# CON_MEZZANINE_GPIO_JTAG.net
KiCad netlist of a schematic drawn in Altium Designer
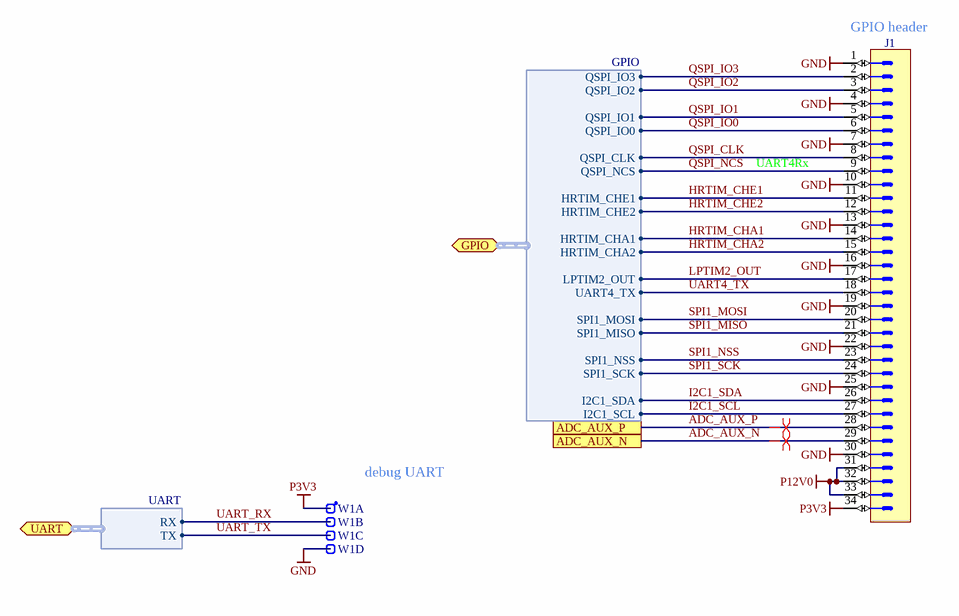
[diagram p0: CON_MEZZANINE_GPIO_JTAG.SchDoc]

(export (version "E")
  (design (tool "Eeschema 10.0.6"))
  (components
    (comp (ref "J1")
      (value "Header 34")
      (footprint "3M_N2534-6002RB")
      (description "Connector 34 Male")
      (fields
        (field (name "PART NUMBER") "3M_N2534-6002RB")
        (field (name "MANUFACTURER") "3M")
        (field (name "AUTHOR") "CERN DEM JLC")
      )
      (libsource (lib "Connectors") (part "Connector 34 Male"))
    )
    (comp (ref "W1")
      (value "Header 4")
      (footprint "SAMTEC_HTSW-104-23-L-S")
      (description "4 Mini Wire-Wrap Contact Strip Header")
      (fields
        (field (name "PART NUMBER") "SAMTEC_HTSW-104-23-L-S")
        (field (name "MANUFACTURER") "SAMTEC")
        (field (name "AUTHOR") "CERN DEM JLC")
      )
      (libsource (lib "Connectors") (part "Wire-Wrap Contact x4"))
    )
  )
  (nets
    (net (code "3") (name "/ADC_AUX_N") (class "Default")
      (node (ref "J1") (pin "29") (pinfunction "29_29") (pintype "bidirectional"))
    )
    (net (code "4") (name "/ADC_AUX_P") (class "Default")
      (node (ref "J1") (pin "28") (pinfunction "28_28") (pintype "bidirectional"))
    )
    (net (code "5") (name "/HRTIM_CHA1") (class "Default")
      (node (ref "J1") (pin "14") (pinfunction "14_14") (pintype "bidirectional"))
    )
    (net (code "6") (name "/HRTIM_CHA2") (class "Default")
      (node (ref "J1") (pin "15") (pinfunction "15_15") (pintype "bidirectional"))
    )
    (net (code "7") (name "/HRTIM_CHE1") (class "Default")
      (node (ref "J1") (pin "11") (pinfunction "11_11") (pintype "bidirectional"))
    )
    (net (code "8") (name "/HRTIM_CHE2") (class "Default")
      (node (ref "J1") (pin "12") (pinfunction "12_12") (pintype "bidirectional"))
    )
    (net (code "9") (name "/I2C1_SCL") (class "Default")
      (node (ref "J1") (pin "27") (pinfunction "27_27") (pintype "bidirectional"))
    )
    (net (code "10") (name "/I2C1_SDA") (class "Default")
      (node (ref "J1") (pin "26") (pinfunction "26_26") (pintype "bidirectional"))
    )
    (net (code "11") (name "/LPTIM2_OUT") (class "Default")
      (node (ref "J1") (pin "17") (pinfunction "17_17") (pintype "bidirectional"))
    )
    (net (code "12") (name "/QSPI_CLK") (class "Default")
      (node (ref "J1") (pin "8") (pinfunction "8_8") (pintype "bidirectional"))
    )
    (net (code "13") (name "/QSPI_IO0") (class "Default")
      (node (ref "J1") (pin "6") (pinfunction "6_6") (pintype "bidirectional"))
    )
    (net (code "14") (name "/QSPI_IO1") (class "Default")
      (node (ref "J1") (pin "5") (pinfunction "5_5") (pintype "bidirectional"))
    )
    (net (code "15") (name "/QSPI_IO2") (class "Default")
      (node (ref "J1") (pin "3") (pinfunction "3_3") (pintype "bidirectional"))
    )
    (net (code "16") (name "/QSPI_IO3") (class "Default")
      (node (ref "J1") (pin "2") (pinfunction "2_2") (pintype "bidirectional"))
    )
    (net (code "17") (name "/QSPI_NCS") (class "Default")
      (node (ref "J1") (pin "9") (pinfunction "9_9") (pintype "bidirectional"))
    )
    (net (code "18") (name "/SPI1_MISO") (class "Default")
      (node (ref "J1") (pin "21") (pinfunction "21_21") (pintype "bidirectional"))
    )
    (net (code "19") (name "/SPI1_MOSI") (class "Default")
      (node (ref "J1") (pin "20") (pinfunction "20_20") (pintype "bidirectional"))
    )
    (net (code "20") (name "/SPI1_NSS") (class "Default")
      (node (ref "J1") (pin "23") (pinfunction "23_23") (pintype "bidirectional"))
    )
    (net (code "21") (name "/SPI1_SCK") (class "Default")
      (node (ref "J1") (pin "24") (pinfunction "24_24") (pintype "bidirectional"))
    )
    (net (code "22") (name "/UART4_TX") (class "Default")
      (node (ref "J1") (pin "18") (pinfunction "18_18") (pintype "bidirectional"))
    )
    (net (code "23") (name "/UART_RX") (class "Default")
      (node (ref "W1") (pin "2") (pinfunction "2_2") (pintype "bidirectional"))
    )
    (net (code "24") (name "/UART_TX") (class "Default")
      (node (ref "W1") (pin "3") (pinfunction "3_3") (pintype "bidirectional"))
    )
    (net (code "27") (name "GND") (class "Default")
      (node (ref "J1") (pin "1") (pinfunction "1_1") (pintype "bidirectional"))
      (node (ref "J1") (pin "10") (pinfunction "10_10") (pintype "bidirectional"))
      (node (ref "J1") (pin "13") (pinfunction "13_13") (pintype "bidirectional"))
      (node (ref "J1") (pin "16") (pinfunction "16_16") (pintype "bidirectional"))
      (node (ref "J1") (pin "19") (pinfunction "19_19") (pintype "bidirectional"))
      (node (ref "J1") (pin "22") (pinfunction "22_22") (pintype "bidirectional"))
      (node (ref "J1") (pin "25") (pinfunction "25_25") (pintype "bidirectional"))
      (node (ref "J1") (pin "30") (pinfunction "30_30") (pintype "bidirectional"))
      (node (ref "J1") (pin "4") (pinfunction "4_4") (pintype "bidirectional"))
      (node (ref "J1") (pin "7") (pinfunction "7_7") (pintype "bidirectional"))
      (node (ref "W1") (pin "4") (pinfunction "4_4") (pintype "bidirectional"))
    )
    (net (code "28") (name "P3V3") (class "Default")
      (node (ref "J1") (pin "34") (pinfunction "34_34") (pintype "bidirectional"))
      (node (ref "W1") (pin "1") (pinfunction "1_1") (pintype "bidirectional"))
    )
    (net (code "29") (name "P12V0") (class "Default")
      (node (ref "J1") (pin "31") (pinfunction "31_31") (pintype "bidirectional"))
      (node (ref "J1") (pin "32") (pinfunction "32_32") (pintype "bidirectional"))
      (node (ref "J1") (pin "33") (pinfunction "33_33") (pintype "bidirectional"))
    )
  )
)
